# STM32-ROMI_Rev_A_5_IMU_IO.net
KiCad netlist of a schematic drawn in Altium Designer
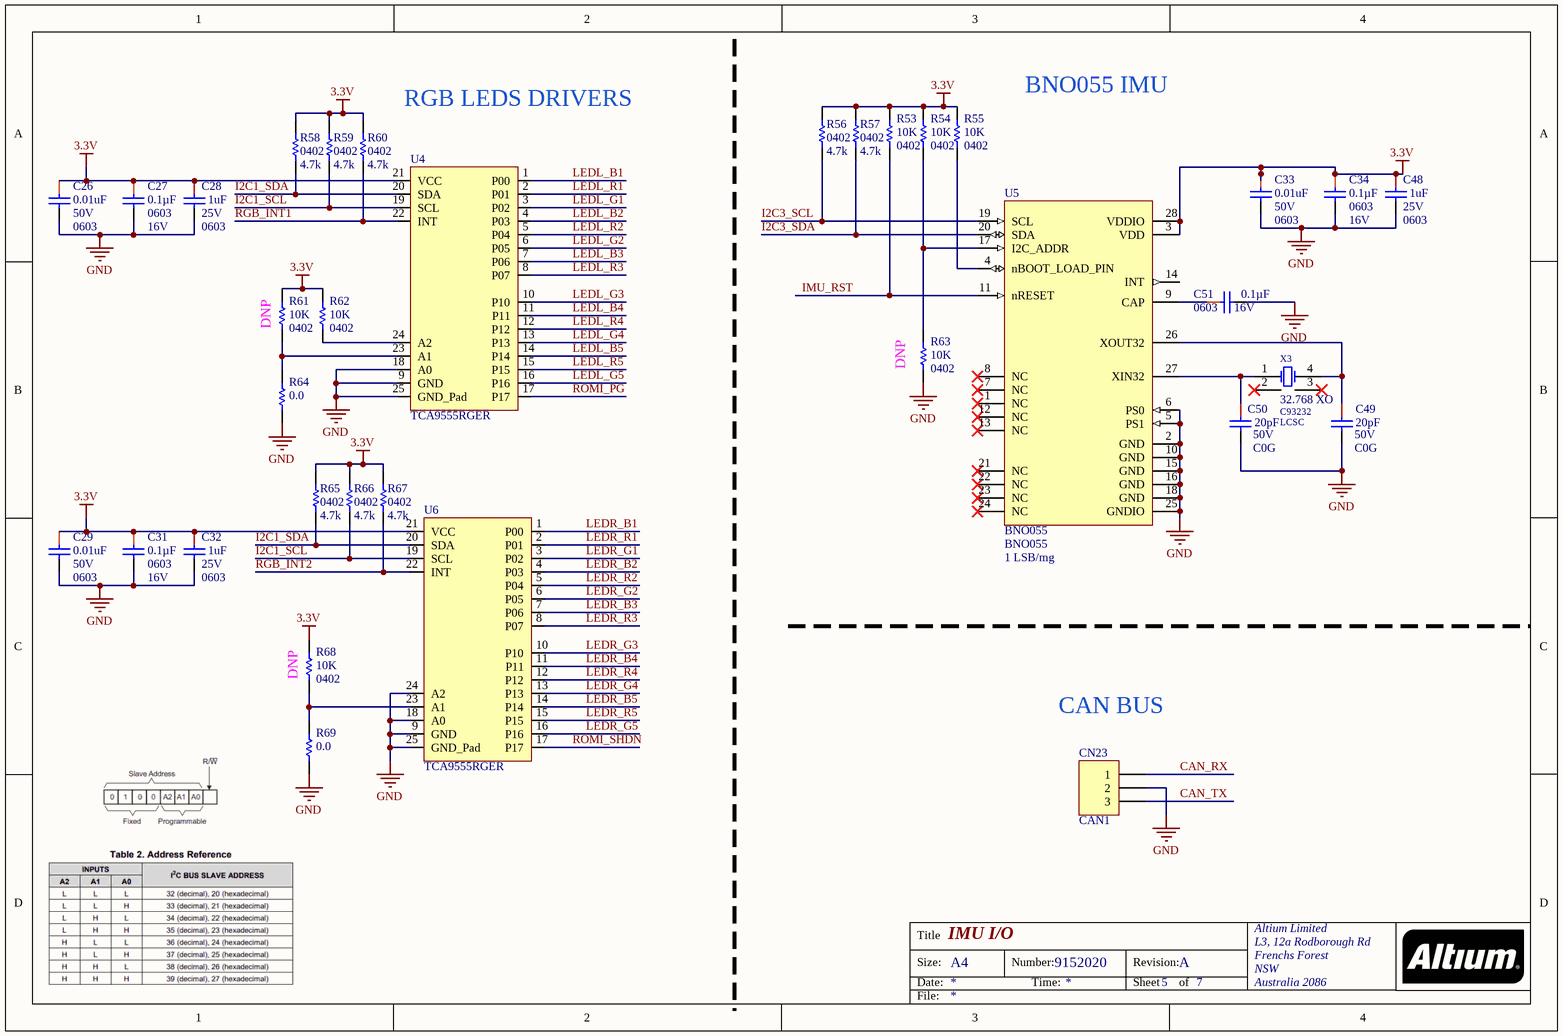
[diagram p0: STM32-ROMI_Rev_A_5_IMU_IO.SchDoc]

(export (version "E")
  (design (tool "Eeschema 10.0.6"))
  (components
    (comp (ref "C26")
      (value "0.01uF")
      (footprint "CAPC0603(1608)_L")
      (description "0.01uF 50V 0603")
      (fields
        (field (name "MANUFACTURER") "Kemet")
        (field (name "MANUFACTURER PART NUMBER") "C0603C103K5RACTU")
        (field (name "VOLTAGE - RATED") "50V")
        (field (name "PACKAGE / CASE") "0603")
      )
      (libsource (lib "OLogic-Passive") (part "CAP CER 0.01uF 50V 10% X7R 0603"))
    )
    (comp (ref "C27")
      (value "0.1uF")
      (footprint "CAPC0603(1608)_L")
      (description "0.1uF 0603 16V")
      (fields
        (field (name "MANUFACTURER") "Kemet")
        (field (name "MANUFACTURER PART NUMBER") "C0603C104K4RACTU")
        (field (name "CAPACITANCE") "0.1µF")
        (field (name "PACKAGE / CASE") "0603")
        (field (name "VOLTAGE - RATED") "16V")
      )
      (libsource (lib "JLCPCB_Passives") (part "CAP CER 0.1UF 16V 10% X7R 0603"))
    )
    (comp (ref "C28")
      (value "1uF")
      (footprint "CAPC0603(1608)_N")
      (description "1uF 0603 25V")
      (fields
        (field (name "MANUFACTURER") "TDK Corporation")
        (field (name "MANUFACTURER PART NUMBER") "CGA3E1X7R1E105K080AC")
        (field (name "VOLTAGE - RATED") "25V")
        (field (name "PACKAGE / CASE") "0603")
      )
      (libsource (lib "OLogic-Passive") (part "CAP CER 1UF 25V 10% X7R 0603"))
    )
    (comp (ref "C29")
      (value "0.01uF")
      (footprint "CAPC0603(1608)_L")
      (description "0.01uF 50V 0603")
      (fields
        (field (name "MANUFACTURER") "Kemet")
        (field (name "MANUFACTURER PART NUMBER") "C0603C103K5RACTU")
        (field (name "VOLTAGE - RATED") "50V")
        (field (name "PACKAGE / CASE") "0603")
      )
      (libsource (lib "OLogic-Passive") (part "CAP CER 0.01uF 50V 10% X7R 0603"))
    )
    (comp (ref "C31")
      (value "0.1uF")
      (footprint "CAPC0603(1608)_L")
      (description "0.1uF 0603 16V")
      (fields
        (field (name "MANUFACTURER") "Kemet")
        (field (name "MANUFACTURER PART NUMBER") "C0603C104K4RACTU")
        (field (name "CAPACITANCE") "0.1µF")
        (field (name "PACKAGE / CASE") "0603")
        (field (name "VOLTAGE - RATED") "16V")
      )
      (libsource (lib "JLCPCB_Passives") (part "CAP CER 0.1UF 16V 10% X7R 0603"))
    )
    (comp (ref "C32")
      (value "1uF")
      (footprint "CAPC0603(1608)_N")
      (description "1uF 0603 25V")
      (fields
        (field (name "MANUFACTURER") "TDK Corporation")
        (field (name "MANUFACTURER PART NUMBER") "CGA3E1X7R1E105K080AC")
        (field (name "VOLTAGE - RATED") "25V")
        (field (name "PACKAGE / CASE") "0603")
      )
      (libsource (lib "OLogic-Passive") (part "CAP CER 1UF 25V 10% X7R 0603"))
    )
    (comp (ref "C33")
      (value "0.01uF")
      (footprint "CAPC0603(1608)_L")
      (description "0.01uF 50V 0603")
      (fields
        (field (name "MANUFACTURER") "Kemet")
        (field (name "MANUFACTURER PART NUMBER") "C0603C103K5RACTU")
        (field (name "VOLTAGE - RATED") "50V")
        (field (name "PACKAGE / CASE") "0603")
      )
      (libsource (lib "OLogic-Passive") (part "CAP CER 0.01uF 50V 10% X7R 0603"))
    )
    (comp (ref "C34")
      (value "0.1uF")
      (footprint "CAPC0603(1608)_L")
      (description "0.1uF 0603 16V")
      (fields
        (field (name "MANUFACTURER") "Kemet")
        (field (name "MANUFACTURER PART NUMBER") "C0603C104K4RACTU")
        (field (name "CAPACITANCE") "0.1µF")
        (field (name "PACKAGE / CASE") "0603")
        (field (name "VOLTAGE - RATED") "16V")
      )
      (libsource (lib "JLCPCB_Passives") (part "CAP CER 0.1UF 16V 10% X7R 0603"))
    )
    (comp (ref "C48")
      (value "1uF")
      (footprint "CAPC0603(1608)_N")
      (description "1uF 0603 25V")
      (fields
        (field (name "MANUFACTURER") "TDK Corporation")
        (field (name "MANUFACTURER PART NUMBER") "CGA3E1X7R1E105K080AC")
        (field (name "VOLTAGE - RATED") "25V")
        (field (name "PACKAGE / CASE") "0603")
      )
      (libsource (lib "OLogic-Passive") (part "CAP CER 1UF 25V 10% X7R 0603"))
    )
    (comp (ref "C49")
      (value "20pF 0402")
      (footprint "CAPC0402(1005)_L")
      (fields
        (field (name "MANUFACTURER") "Murata Electronics North America")
        (field (name "MANUFACTURER PART NUMBER") "GRM1555C1H200GA01D")
        (field (name "VOLTAGE - RATED") "50V")
        (field (name "TEMPERATURE COEFFICIENT") "C0G")
        (field (name "CAPACITANCE") "20pF")
        (field (name "TOLERANCE") "±2%")
        (field (name "CREATOR") "osman")
      )
      (libsource (lib "OLogic-Passive") (part "CAP CER 20PF 50V 2% NP0 0402"))
    )
    (comp (ref "C50")
      (value "20pF 0402")
      (footprint "CAPC0402(1005)_L")
      (fields
        (field (name "MANUFACTURER") "Murata Electronics North America")
        (field (name "MANUFACTURER PART NUMBER") "GRM1555C1H200GA01D")
        (field (name "VOLTAGE - RATED") "50V")
        (field (name "TEMPERATURE COEFFICIENT") "C0G")
        (field (name "CAPACITANCE") "20pF")
        (field (name "TOLERANCE") "±2%")
        (field (name "CREATOR") "osman")
      )
      (libsource (lib "OLogic-Passive") (part "CAP CER 20PF 50V 2% NP0 0402"))
    )
    (comp (ref "C51")
      (value "0.1uF")
      (footprint "CAPC0603(1608)_L")
      (description "0.1uF 0603 16V")
      (fields
        (field (name "MANUFACTURER") "Kemet")
        (field (name "MANUFACTURER PART NUMBER") "C0603C104K4RACTU")
        (field (name "CAPACITANCE") "0.1µF")
        (field (name "PACKAGE / CASE") "0603")
        (field (name "VOLTAGE - RATED") "16V")
      )
      (libsource (lib "JLCPCB_Passives") (part "CAP CER 0.1UF 16V 10% X7R 0603"))
    )
    (comp (ref "CN23")
      (value "CAN1")
      (footprint "HDR1X3")
      (description "Header, 3-Pin")
      (fields
        (field (name "MANUFACTURER") "Sullins Connector Solutions")
        (field (name "MANUFACTURER PART NUMBER") "PRPC003SAAN-RC")
      )
      (libsource (lib "Kyle-Connectors") (part "Header 3"))
    )
    (comp (ref "R53")
      (value "10K")
      (footprint "RESC0402(1005)_N")
      (description "10K 0402")
      (fields
        (field (name "MANUFACTURER") "Samsung Electro-Mechanics")
        (field (name "MANUFACTURER PART NUMBER") "RC1005F103CS")
        (field (name "SUPPLIER DEVICE PACKAGE") "0402")
      )
      (libsource (lib "OLogic-Passive") (part "RES 10K OHM 1% 1/16W 0402"))
    )
    (comp (ref "R54")
      (value "10K")
      (footprint "RESC0402(1005)_N")
      (description "10K 0402")
      (fields
        (field (name "MANUFACTURER") "Samsung Electro-Mechanics")
        (field (name "MANUFACTURER PART NUMBER") "RC1005F103CS")
        (field (name "SUPPLIER DEVICE PACKAGE") "0402")
      )
      (libsource (lib "OLogic-Passive") (part "RES 10K OHM 1% 1/16W 0402"))
    )
    (comp (ref "R55")
      (value "10K")
      (footprint "RESC0402(1005)_N")
      (description "10K 0402")
      (fields
        (field (name "MANUFACTURER") "Samsung Electro-Mechanics")
        (field (name "MANUFACTURER PART NUMBER") "RC1005F103CS")
        (field (name "SUPPLIER DEVICE PACKAGE") "0402")
      )
      (libsource (lib "OLogic-Passive") (part "RES 10K OHM 1% 1/16W 0402"))
    )
    (comp (ref "R56")
      (value "4.7K")
      (footprint "RESC0402(1005)_N")
      (description "4.7K 0402")
      (fields
        (field (name "MANUFACTURER") "Yageo")
        (field (name "MANUFACTURER PART NUMBER") "RC0402FR-074K7L")
        (field (name "PACKAGE / CASE") "0402")
        (field (name "RESISTANCE (OHMS)") "4.7k")
      )
      (libsource (lib "OLogic-Passive") (part "RES 4.7K OHM 1% 1/10W 0402"))
    )
    (comp (ref "R57")
      (value "4.7K")
      (footprint "RESC0402(1005)_N")
      (description "4.7K 0402")
      (fields
        (field (name "MANUFACTURER") "Yageo")
        (field (name "MANUFACTURER PART NUMBER") "RC0402FR-074K7L")
        (field (name "PACKAGE / CASE") "0402")
        (field (name "RESISTANCE (OHMS)") "4.7k")
      )
      (libsource (lib "OLogic-Passive") (part "RES 4.7K OHM 1% 1/10W 0402"))
    )
    (comp (ref "R58")
      (value "4.7K")
      (footprint "RESC0402(1005)_N")
      (description "4.7K 0402")
      (fields
        (field (name "MANUFACTURER") "Yageo")
        (field (name "MANUFACTURER PART NUMBER") "RC0402FR-074K7L")
        (field (name "PACKAGE / CASE") "0402")
        (field (name "RESISTANCE (OHMS)") "4.7k")
      )
      (libsource (lib "OLogic-Passive") (part "RES 4.7K OHM 1% 1/10W 0402"))
    )
    (comp (ref "R59")
      (value "4.7K")
      (footprint "RESC0402(1005)_N")
      (description "4.7K 0402")
      (fields
        (field (name "MANUFACTURER") "Yageo")
        (field (name "MANUFACTURER PART NUMBER") "RC0402FR-074K7L")
        (field (name "PACKAGE / CASE") "0402")
        (field (name "RESISTANCE (OHMS)") "4.7k")
      )
      (libsource (lib "OLogic-Passive") (part "RES 4.7K OHM 1% 1/10W 0402"))
    )
    (comp (ref "R60")
      (value "4.7K")
      (footprint "RESC0402(1005)_N")
      (description "4.7K 0402")
      (fields
        (field (name "MANUFACTURER") "Yageo")
        (field (name "MANUFACTURER PART NUMBER") "RC0402FR-074K7L")
        (field (name "PACKAGE / CASE") "0402")
        (field (name "RESISTANCE (OHMS)") "4.7k")
      )
      (libsource (lib "OLogic-Passive") (part "RES 4.7K OHM 1% 1/10W 0402"))
    )
    (comp (ref "R61")
      (value "10K")
      (footprint "RESC0402(1005)_N")
      (description "10K 0402")
      (fields
        (field (name "MANUFACTURER") "Samsung Electro-Mechanics")
        (field (name "MANUFACTURER PART NUMBER") "RC1005F103CS")
        (field (name "SUPPLIER DEVICE PACKAGE") "0402")
      )
      (libsource (lib "OLogic-Passive") (part "RES 10K OHM 1% 1/16W 0402"))
    )
    (comp (ref "R62")
      (value "10K")
      (footprint "RESC0402(1005)_N")
      (description "10K 0402")
      (fields
        (field (name "MANUFACTURER") "Samsung Electro-Mechanics")
        (field (name "MANUFACTURER PART NUMBER") "RC1005F103CS")
        (field (name "SUPPLIER DEVICE PACKAGE") "0402")
      )
      (libsource (lib "OLogic-Passive") (part "RES 10K OHM 1% 1/16W 0402"))
    )
    (comp (ref "R63")
      (value "10K")
      (footprint "RESC0402(1005)_N")
      (description "10K 0402")
      (fields
        (field (name "MANUFACTURER") "Samsung Electro-Mechanics")
        (field (name "MANUFACTURER PART NUMBER") "RC1005F103CS")
        (field (name "SUPPLIER DEVICE PACKAGE") "0402")
      )
      (libsource (lib "OLogic-Passive") (part "RES 10K OHM 1% 1/16W 0402"))
    )
    (comp (ref "R64")
      (value "0")
      (footprint "RESC0402(1005)_L")
      (description "0.0 0402")
      (fields
        (field (name "MANUFACTURER") "Panasonic Electronic Components")
        (field (name "MANUFACTURER PART NUMBER") "ERJ-2GE0R00X")
        (field (name "RESISTANCE (OHMS)") "0.0")
        (field (name "CREATOR") "osman")
      )
      (libsource (lib "OLogic-Passive") (part "RES 0.0 OHM JUMPER 1/10W 0402"))
    )
    (comp (ref "R65")
      (value "4.7K")
      (footprint "RESC0402(1005)_N")
      (description "4.7K 0402")
      (fields
        (field (name "MANUFACTURER") "Yageo")
        (field (name "MANUFACTURER PART NUMBER") "RC0402FR-074K7L")
        (field (name "PACKAGE / CASE") "0402")
        (field (name "RESISTANCE (OHMS)") "4.7k")
      )
      (libsource (lib "OLogic-Passive") (part "RES 4.7K OHM 1% 1/10W 0402"))
    )
    (comp (ref "R66")
      (value "4.7K")
      (footprint "RESC0402(1005)_N")
      (description "4.7K 0402")
      (fields
        (field (name "MANUFACTURER") "Yageo")
        (field (name "MANUFACTURER PART NUMBER") "RC0402FR-074K7L")
        (field (name "PACKAGE / CASE") "0402")
        (field (name "RESISTANCE (OHMS)") "4.7k")
      )
      (libsource (lib "OLogic-Passive") (part "RES 4.7K OHM 1% 1/10W 0402"))
    )
    (comp (ref "R67")
      (value "4.7K")
      (footprint "RESC0402(1005)_N")
      (description "4.7K 0402")
      (fields
        (field (name "MANUFACTURER") "Yageo")
        (field (name "MANUFACTURER PART NUMBER") "RC0402FR-074K7L")
        (field (name "PACKAGE / CASE") "0402")
        (field (name "RESISTANCE (OHMS)") "4.7k")
      )
      (libsource (lib "OLogic-Passive") (part "RES 4.7K OHM 1% 1/10W 0402"))
    )
    (comp (ref "R68")
      (value "10K")
      (footprint "RESC0402(1005)_N")
      (description "10K 0402")
      (fields
        (field (name "MANUFACTURER") "Samsung Electro-Mechanics")
        (field (name "MANUFACTURER PART NUMBER") "RC1005F103CS")
        (field (name "SUPPLIER DEVICE PACKAGE") "0402")
      )
      (libsource (lib "OLogic-Passive") (part "RES 10K OHM 1% 1/16W 0402"))
    )
    (comp (ref "R69")
      (value "0")
      (footprint "RESC0402(1005)_L")
      (description "0.0 0402")
      (fields
        (field (name "MANUFACTURER") "Panasonic Electronic Components")
        (field (name "MANUFACTURER PART NUMBER") "ERJ-2GE0R00X")
        (field (name "RESISTANCE (OHMS)") "0.0")
        (field (name "CREATOR") "osman")
      )
      (libsource (lib "OLogic-Passive") (part "RES 0.0 OHM JUMPER 1/10W 0402"))
    )
    (comp (ref "U4")
      (value "TCA9555RGER")
      (footprint "QFN50P400X400X100_HS-25N")
      (description "IC I/O EXPANDER I2C SMBUS 24VQFN")
      (fields (field (name "MANUFACTURER") "Texas Instruments"))
      (libsource (lib "JLCPCB_CPU") (part "CMP-001-0784-04"))
    )
    (comp (ref "U5")
      (value "BNO055")
      (footprint "LGA-28-3.8x5.2mm")
      (description "9-Axis Intertial Sensor")
      (fields
        (field (name "MANUFACTURER") "Bosch Tools")
        (field (name "MANUFACTURER PART NUMBER") "BNO055")
        (field (name "SENSITIVITY") "1 LSB/mg")
      )
      (libsource (lib "JLCPCB_CPU") (part "CMP-010-0024-02"))
    )
    (comp (ref "U6")
      (value "TCA9555RGER")
      (footprint "QFN50P400X400X100_HS-25N")
      (description "IC I/O EXPANDER I2C SMBUS 24VQFN")
      (fields (field (name "MANUFACTURER") "Texas Instruments"))
      (libsource (lib "JLCPCB_CPU") (part "CMP-001-0784-04"))
    )
    (comp (ref "X3")
      (value "32.768 XO")
      (footprint "OSCABS")
      (description "SMD CRYSTAL RESONATORS 32.768KHZ ±20PPM SMD-3215_2P ROHS")
      (fields (field (name "SUPPLIER PART NUMBER 2") "C93232") (field (name "SUPPLIER 2") "LCSC"))
      (libsource (lib "JLCPCB_RF-OSC") (part "DST310S 32.768KHz"))
    )
  )
  (nets
    (net (code "1") (name "/CAN_RX") (class "Default")
      (node (ref "CN23") (pin "1") (pinfunction "1_1") (pintype "passive"))
    )
    (net (code "2") (name "/CAN_TX") (class "Default")
      (node (ref "CN23") (pin "3") (pinfunction "3_3") (pintype "passive"))
    )
    (net (code "3") (name "/I2C1_SCL") (class "Default")
      (node (ref "R59") (pin "1") (pinfunction "1_1") (pintype "passive"))
      (node (ref "R66") (pin "1") (pinfunction "1_1") (pintype "passive"))
      (node (ref "U4") (pin "19") (pinfunction "SCL_19") (pintype "bidirectional"))
      (node (ref "U6") (pin "19") (pinfunction "SCL_19") (pintype "bidirectional"))
    )
    (net (code "4") (name "/I2C1_SDA") (class "Default")
      (node (ref "R58") (pin "1") (pinfunction "1_1") (pintype "passive"))
      (node (ref "R65") (pin "1") (pinfunction "1_1") (pintype "passive"))
      (node (ref "U4") (pin "20") (pinfunction "SDA_20") (pintype "bidirectional"))
      (node (ref "U6") (pin "20") (pinfunction "SDA_20") (pintype "bidirectional"))
    )
    (net (code "5") (name "/I2C3_SCL") (class "Default")
      (node (ref "R56") (pin "1") (pinfunction "1_1") (pintype "passive"))
      (node (ref "U5") (pin "19") (pinfunction "SCL_19") (pintype "input"))
    )
    (net (code "6") (name "/I2C3_SDA") (class "Default")
      (node (ref "R57") (pin "1") (pinfunction "1_1") (pintype "passive"))
      (node (ref "U5") (pin "20") (pinfunction "SDA_20") (pintype "bidirectional"))
    )
    (net (code "7") (name "/IMU_RST") (class "Default")
      (node (ref "R53") (pin "1") (pinfunction "1_1") (pintype "passive"))
      (node (ref "U5") (pin "11") (pinfunction "nRESET_11") (pintype "input"))
    )
    (net (code "8") (name "/LEDL_B1") (class "Default")
      (node (ref "U4") (pin "1") (pinfunction "P00_1") (pintype "passive"))
    )
    (net (code "9") (name "/LEDL_B2") (class "Default")
      (node (ref "U4") (pin "4") (pinfunction "P03_4") (pintype "passive"))
    )
    (net (code "10") (name "/LEDL_B3") (class "Default")
      (node (ref "U4") (pin "7") (pinfunction "P06_7") (pintype "passive"))
    )
    (net (code "11") (name "/LEDL_B4") (class "Default")
      (node (ref "U4") (pin "11") (pinfunction "P11_11") (pintype "passive"))
    )
    (net (code "12") (name "/LEDL_B5") (class "Default")
      (node (ref "U4") (pin "14") (pinfunction "P14_14") (pintype "passive"))
    )
    (net (code "13") (name "/LEDL_G1") (class "Default")
      (node (ref "U4") (pin "3") (pinfunction "P02_3") (pintype "passive"))
    )
    (net (code "14") (name "/LEDL_G2") (class "Default")
      (node (ref "U4") (pin "6") (pinfunction "P05_6") (pintype "passive"))
    )
    (net (code "15") (name "/LEDL_G3") (class "Default")
      (node (ref "U4") (pin "10") (pinfunction "P10_10") (pintype "passive"))
    )
    (net (code "16") (name "/LEDL_G4") (class "Default")
      (node (ref "U4") (pin "13") (pinfunction "P13_13") (pintype "passive"))
    )
    (net (code "17") (name "/LEDL_G5") (class "Default")
      (node (ref "U4") (pin "16") (pinfunction "P16_16") (pintype "passive"))
    )
    (net (code "18") (name "/LEDL_R1") (class "Default")
      (node (ref "U4") (pin "2") (pinfunction "P01_2") (pintype "passive"))
    )
    (net (code "19") (name "/LEDL_R2") (class "Default")
      (node (ref "U4") (pin "5") (pinfunction "P04_5") (pintype "passive"))
    )
    (net (code "20") (name "/LEDL_R3") (class "Default")
      (node (ref "U4") (pin "8") (pinfunction "P07_8") (pintype "passive"))
    )
    (net (code "21") (name "/LEDL_R4") (class "Default")
      (node (ref "U4") (pin "12") (pinfunction "P12_12") (pintype "passive"))
    )
    (net (code "22") (name "/LEDL_R5") (class "Default")
      (node (ref "U4") (pin "15") (pinfunction "P15_15") (pintype "passive"))
    )
    (net (code "23") (name "/LEDR_B1") (class "Default")
      (node (ref "U6") (pin "1") (pinfunction "P00_1") (pintype "passive"))
    )
    (net (code "24") (name "/LEDR_B2") (class "Default")
      (node (ref "U6") (pin "4") (pinfunction "P03_4") (pintype "passive"))
    )
    (net (code "25") (name "/LEDR_B3") (class "Default")
      (node (ref "U6") (pin "7") (pinfunction "P06_7") (pintype "passive"))
    )
    (net (code "26") (name "/LEDR_B4") (class "Default")
      (node (ref "U6") (pin "11") (pinfunction "P11_11") (pintype "passive"))
    )
    (net (code "27") (name "/LEDR_B5") (class "Default")
      (node (ref "U6") (pin "14") (pinfunction "P14_14") (pintype "passive"))
    )
    (net (code "28") (name "/LEDR_G1") (class "Default")
      (node (ref "U6") (pin "3") (pinfunction "P02_3") (pintype "passive"))
    )
    (net (code "29") (name "/LEDR_G2") (class "Default")
      (node (ref "U6") (pin "6") (pinfunction "P05_6") (pintype "passive"))
    )
    (net (code "30") (name "/LEDR_G3") (class "Default")
      (node (ref "U6") (pin "10") (pinfunction "P10_10") (pintype "passive"))
    )
    (net (code "31") (name "/LEDR_G4") (class "Default")
      (node (ref "U6") (pin "13") (pinfunction "P13_13") (pintype "passive"))
    )
    (net (code "32") (name "/LEDR_G5") (class "Default")
      (node (ref "U6") (pin "16") (pinfunction "P16_16") (pintype "passive"))
    )
    (net (code "33") (name "/LEDR_R1") (class "Default")
      (node (ref "U6") (pin "2") (pinfunction "P01_2") (pintype "passive"))
    )
    (net (code "34") (name "/LEDR_R2") (class "Default")
      (node (ref "U6") (pin "5") (pinfunction "P04_5") (pintype "passive"))
    )
    (net (code "35") (name "/LEDR_R3") (class "Default")
      (node (ref "U6") (pin "8") (pinfunction "P07_8") (pintype "passive"))
    )
    (net (code "36") (name "/LEDR_R4") (class "Default")
      (node (ref "U6") (pin "12") (pinfunction "P12_12") (pintype "passive"))
    )
    (net (code "37") (name "/LEDR_R5") (class "Default")
      (node (ref "U6") (pin "15") (pinfunction "P15_15") (pintype "passive"))
    )
    (net (code "38") (name "/RGB_INT1") (class "Default")
      (node (ref "R60") (pin "1") (pinfunction "1_1") (pintype "passive"))
      (node (ref "U4") (pin "22") (pinfunction "INT_22") (pintype "passive"))
    )
    (net (code "39") (name "/RGB_INT2") (class "Default")
      (node (ref "R67") (pin "1") (pinfunction "1_1") (pintype "passive"))
      (node (ref "U6") (pin "22") (pinfunction "INT_22") (pintype "passive"))
    )
    (net (code "40") (name "/ROMI_PG") (class "Default")
      (node (ref "U4") (pin "17") (pinfunction "P17_17") (pintype "passive"))
    )
    (net (code "41") (name "/ROMI_SHDN") (class "Default")
      (node (ref "U6") (pin "17") (pinfunction "P17_17") (pintype "passive"))
    )
    (net (code "42") (name "3.3V") (class "Default")
      (node (ref "C26") (pin "1") (pinfunction "1_1") (pintype "passive"))
      (node (ref "C27") (pin "1") (pinfunction "1_1") (pintype "passive"))
      (node (ref "C28") (pin "1") (pinfunction "1_1") (pintype "passive"))
      (node (ref "C29") (pin "1") (pinfunction "1_1") (pintype "passive"))
      (node (ref "C31") (pin "1") (pinfunction "1_1") (pintype "passive"))
      (node (ref "C32") (pin "1") (pinfunction "1_1") (pintype "passive"))
      (node (ref "C33") (pin "1") (pinfunction "1_1") (pintype "passive"))
      (node (ref "C34") (pin "1") (pinfunction "1_1") (pintype "passive"))
      (node (ref "C48") (pin "1") (pinfunction "1_1") (pintype "passive"))
      (node (ref "R53") (pin "2") (pinfunction "2_2") (pintype "passive"))
      (node (ref "R54") (pin "2") (pinfunction "2_2") (pintype "passive"))
      (node (ref "R55") (pin "2") (pinfunction "2_2") (pintype "passive"))
      (node (ref "R56") (pin "2") (pinfunction "2_2") (pintype "passive"))
      (node (ref "R57") (pin "2") (pinfunction "2_2") (pintype "passive"))
      (node (ref "R58") (pin "2") (pinfunction "2_2") (pintype "passive"))
      (node (ref "R59") (pin "2") (pinfunction "2_2") (pintype "passive"))
      (node (ref "R60") (pin "2") (pinfunction "2_2") (pintype "passive"))
      (node (ref "R61") (pin "2") (pinfunction "2_2") (pintype "passive"))
      (node (ref "R62") (pin "2") (pinfunction "2_2") (pintype "passive"))
      (node (ref "R65") (pin "2") (pinfunction "2_2") (pintype "passive"))
      (node (ref "R66") (pin "2") (pinfunction "2_2") (pintype "passive"))
      (node (ref "R67") (pin "2") (pinfunction "2_2") (pintype "passive"))
      (node (ref "R68") (pin "2") (pinfunction "2_2") (pintype "passive"))
      (node (ref "U4") (pin "21") (pinfunction "VCC_21") (pintype "power_in"))
      (node (ref "U5") (pin "28") (pinfunction "VDDIO_28") (pintype "power_in"))
      (node (ref "U5") (pin "3") (pinfunction "VDD_3") (pintype "power_in"))
      (node (ref "U6") (pin "21") (pinfunction "VCC_21") (pintype "power_in"))
    )
    (net (code "43") (name "GND") (class "Default")
      (node (ref "C26") (pin "2") (pinfunction "2_2") (pintype "passive"))
      (node (ref "C27") (pin "2") (pinfunction "2_2") (pintype "passive"))
      (node (ref "C28") (pin "2") (pinfunction "2_2") (pintype "passive"))
      (node (ref "C29") (pin "2") (pinfunction "2_2") (pintype "passive"))
      (node (ref "C31") (pin "2") (pinfunction "2_2") (pintype "passive"))
      (node (ref "C32") (pin "2") (pinfunction "2_2") (pintype "passive"))
      (node (ref "C33") (pin "2") (pinfunction "2_2") (pintype "passive"))
      (node (ref "C34") (pin "2") (pinfunction "2_2") (pintype "passive"))
      (node (ref "C48") (pin "2") (pinfunction "2_2") (pintype "passive"))
      (node (ref "C49") (pin "2") (pinfunction "2_2") (pintype "passive"))
      (node (ref "C50") (pin "2") (pinfunction "2_2") (pintype "passive"))
      (node (ref "C51") (pin "2") (pinfunction "2_2") (pintype "passive"))
      (node (ref "CN23") (pin "2") (pinfunction "2_2") (pintype "passive"))
      (node (ref "R63") (pin "1") (pinfunction "1_1") (pintype "passive"))
      (node (ref "R64") (pin "1") (pinfunction "1_1") (pintype "passive"))
      (node (ref "R69") (pin "1") (pinfunction "1_1") (pintype "passive"))
      (node (ref "U4") (pin "18") (pinfunction "A0_18") (pintype "passive"))
      (node (ref "U4") (pin "25") (pinfunction "GND_Pad_25") (pintype "power_in"))
      (node (ref "U4") (pin "9") (pinfunction "GND_9") (pintype "power_in"))
      (node (ref "U5") (pin "10") (pinfunction "GND_10") (pintype "power_in"))
      (node (ref "U5") (pin "15") (pinfunction "GND_15") (pintype "power_in"))
      (node (ref "U5") (pin "16") (pinfunction "GND_16") (pintype "power_in"))
      (node (ref "U5") (pin "18") (pinfunction "GND_18") (pintype "power_in"))
      (node (ref "U5") (pin "2") (pinfunction "GND_2") (pintype "power_in"))
      (node (ref "U5") (pin "25") (pinfunction "GNDIO_25") (pintype "power_in"))
      (node (ref "U5") (pin "5") (pinfunction "PS1_5") (pintype "input"))
      (node (ref "U5") (pin "6") (pinfunction "PS0_6") (pintype "input"))
      (node (ref "U6") (pin "18") (pinfunction "A0_18") (pintype "passive"))
      (node (ref "U6") (pin "24") (pinfunction "A2_24") (pintype "passive"))
      (node (ref "U6") (pin "25") (pinfunction "GND_Pad_25") (pintype "power_in"))
      (node (ref "U6") (pin "9") (pinfunction "GND_9") (pintype "power_in"))
    )
    (net (code "44") (name "Net-(U4-A1)") (class "Default")
      (node (ref "R61") (pin "1") (pinfunction "1_1") (pintype "passive"))
      (node (ref "R64") (pin "2") (pinfunction "2_2") (pintype "passive"))
      (node (ref "U4") (pin "23") (pinfunction "A1_23") (pintype "passive"))
    )
    (net (code "45") (name "Net-(U4-A2)") (class "Default")
      (node (ref "R62") (pin "1") (pinfunction "1_1") (pintype "passive"))
      (node (ref "U4") (pin "24") (pinfunction "A2_24") (pintype "passive"))
    )
    (net (code "46") (name "Net-(U5-CAP)") (class "Default")
      (node (ref "C51") (pin "1") (pinfunction "1_1") (pintype "passive"))
      (node (ref "U5") (pin "9") (pinfunction "CAP_9") (pintype "passive"))
    )
    (net (code "47") (name "Net-(U5-I2C_ADDR)") (class "Default")
      (node (ref "R54") (pin "1") (pinfunction "1_1") (pintype "passive"))
      (node (ref "R63") (pin "2") (pinfunction "2_2") (pintype "passive"))
      (node (ref "U5") (pin "17") (pinfunction "I2C_ADDR_17") (pintype "input"))
    )
    (net (code "48") (name "Net-(U5-XIN32)") (class "Default")
      (node (ref "C50") (pin "1") (pinfunction "1_1") (pintype "passive"))
      (node (ref "U5") (pin "27") (pinfunction "XIN32_27") (pintype "passive"))
      (node (ref "X3") (pin "1") (pinfunction "OSC1_1") (pintype "passive"))
    )
    (net (code "49") (name "Net-(U5-XOUT32)") (class "Default")
      (node (ref "C49") (pin "1") (pinfunction "1_1") (pintype "passive"))
      (node (ref "U5") (pin "26") (pinfunction "XOUT32_26") (pintype "passive"))
      (node (ref "X3") (pin "4") (pinfunction "OSC2_4") (pintype "passive"))
    )
    (net (code "50") (name "Net-(U5-nBOOT_LOAD_PIN)") (class "Default")
      (node (ref "R55") (pin "1") (pinfunction "1_1") (pintype "passive"))
      (node (ref "U5") (pin "4") (pinfunction "nBOOT_LOAD_PIN_4") (pintype "bidirectional"))
    )
    (net (code "51") (name "Net-(U6-A1)") (class "Default")
      (node (ref "R68") (pin "1") (pinfunction "1_1") (pintype "passive"))
      (node (ref "R69") (pin "2") (pinfunction "2_2") (pintype "passive"))
      (node (ref "U6") (pin "23") (pinfunction "A1_23") (pintype "passive"))
    )
    (net (code "52") (name "unconnected-(U5-INT-Pad14)") (class "Default")
      (node (ref "U5") (pin "14") (pinfunction "INT_14") (pintype "output"))
    )
    (net (code "53") (name "unconnected-(U5-NC-Pad1)") (class "Default")
      (node (ref "U5") (pin "1") (pinfunction "NC_1") (pintype "passive+no_connect"))
    )
    (net (code "54") (name "unconnected-(U5-NC-Pad7)") (class "Default")
      (node (ref "U5") (pin "7") (pinfunction "NC_7") (pintype "passive+no_connect"))
    )
    (net (code "55") (name "unconnected-(U5-NC-Pad8)") (class "Default")
      (node (ref "U5") (pin "8") (pinfunction "NC_8") (pintype "passive+no_connect"))
    )
    (net (code "56") (name "unconnected-(U5-NC-Pad12)") (class "Default")
      (node (ref "U5") (pin "12") (pinfunction "NC_12") (pintype "passive+no_connect"))
    )
    (net (code "57") (name "unconnected-(U5-NC-Pad13)") (class "Default")
      (node (ref "U5") (pin "13") (pinfunction "NC_13") (pintype "passive+no_connect"))
    )
    (net (code "58") (name "unconnected-(U5-NC-Pad21)") (class "Default")
      (node (ref "U5") (pin "21") (pinfunction "NC_21") (pintype "passive+no_connect"))
    )
    (net (code "59") (name "unconnected-(U5-NC-Pad22)") (class "Default")
      (node (ref "U5") (pin "22") (pinfunction "NC_22") (pintype "passive+no_connect"))
    )
    (net (code "60") (name "unconnected-(U5-NC-Pad23)") (class "Default")
      (node (ref "U5") (pin "23") (pinfunction "NC_23") (pintype "passive+no_connect"))
    )
    (net (code "61") (name "unconnected-(U5-NC-Pad24)") (class "Default")
      (node (ref "U5") (pin "24") (pinfunction "NC_24") (pintype "passive+no_connect"))
    )
    (net (code "62") (name "unconnected-(X3-NC-Pad2)") (class "Default")
      (node (ref "X3") (pin "2") (pinfunction "NC_2") (pintype "passive+no_connect"))
    )
    (net (code "63") (name "unconnected-(X3-NC-Pad3)") (class "Default")
      (node (ref "X3") (pin "3") (pinfunction "NC_3") (pintype "passive+no_connect"))
    )
  )
)
